# 26_LMS3_RX2_BB_ADC.net
KiCad netlist of a schematic drawn in Altium Designer
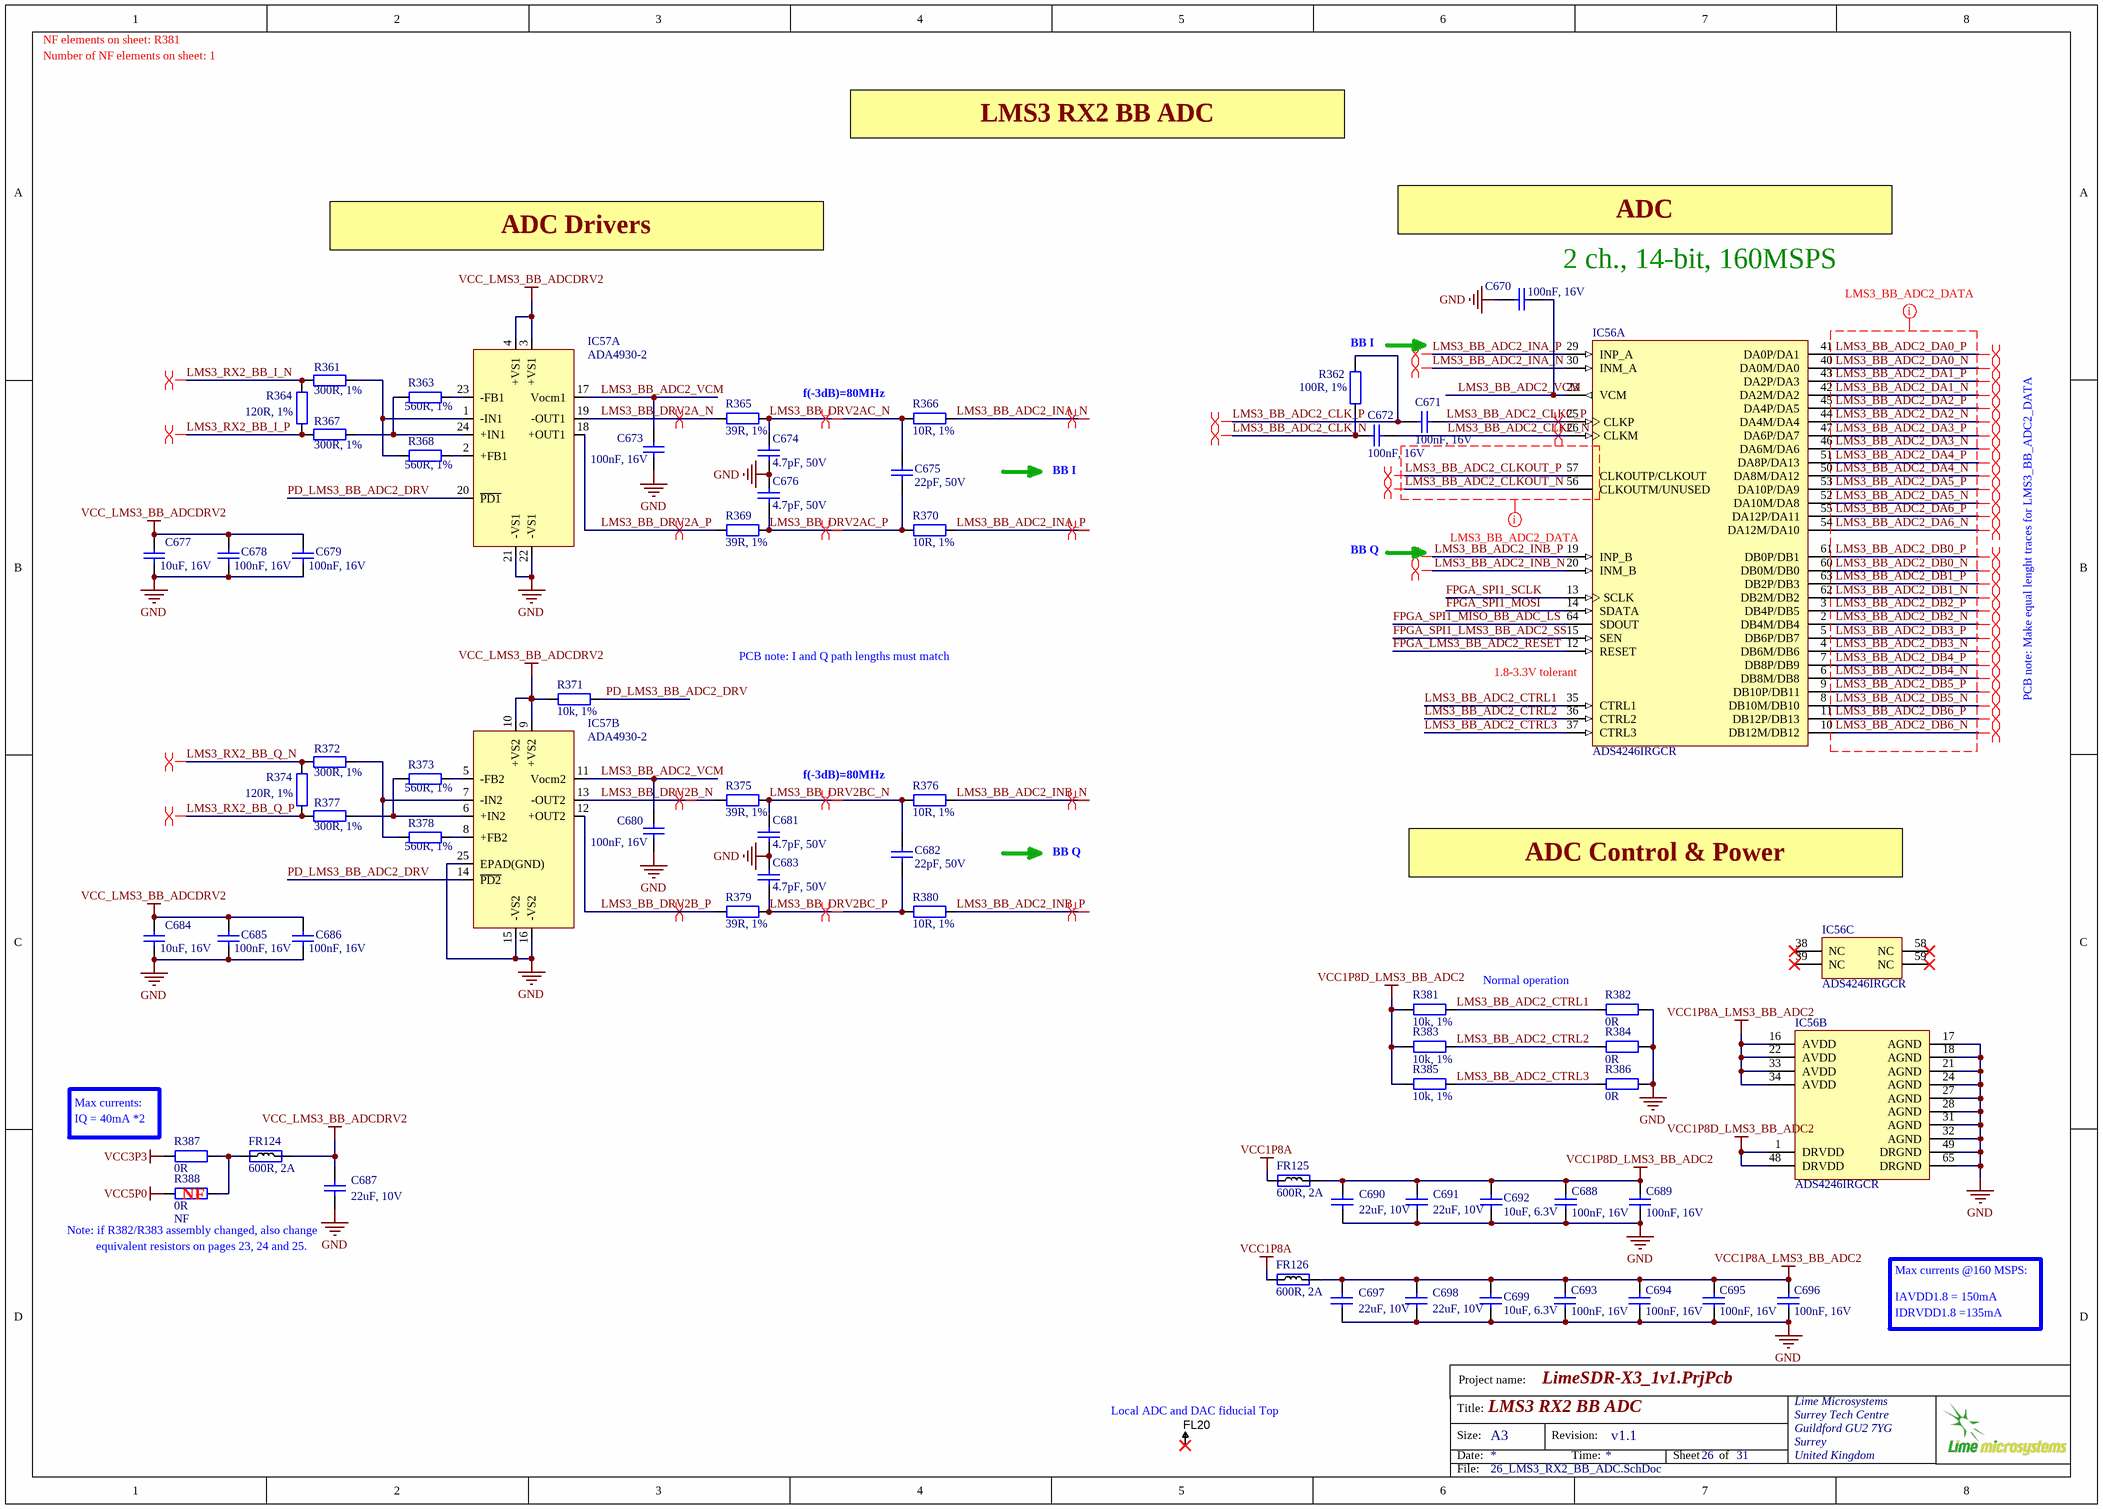
[diagram p0: 26_LMS3_RX2_BB_ADC.SchDoc]

(export (version "E")
  (design (tool "Eeschema 10.0.6"))
  (components
    (comp (ref "C670")
      (value "100nF, 16V")
      (footprint "CAP0402")
      (fields (field (name "TOLERANCE") "10 %") (field (name "MANUFACTURER") "Murata Electronics"))
      (libsource (lib "") (part "Cap_0603_1"))
    )
    (comp (ref "C671")
      (value "100nF, 16V")
      (footprint "CAP0402")
      (fields (field (name "TOLERANCE") "10 %") (field (name "MANUFACTURER") "Murata Electronics"))
      (libsource (lib "") (part "Cap_0603_1"))
    )
    (comp (ref "C672")
      (value "100nF, 16V")
      (footprint "CAP0402")
      (fields (field (name "TOLERANCE") "10 %") (field (name "MANUFACTURER") "Murata Electronics"))
      (libsource (lib "") (part "Cap_0603_4"))
    )
    (comp (ref "C673")
      (value "100nF, 16V")
      (footprint "CAP0402")
      (fields (field (name "TOLERANCE") "10 %") (field (name "MANUFACTURER") "Murata Electronics"))
      (libsource (lib "") (part "Cap_0603_4"))
    )
    (comp (ref "C674")
      (value "4.7pF, 50V")
      (footprint "CAP0402")
      (fields (field (name "MANUFACTURER") "MURATA"))
      (libsource (lib "LimeMicroAltiumLib_schLib") (part "Cap_0402"))
    )
    (comp (ref "C675")
      (value "22pF, 50V")
      (footprint "CAP0402")
      (fields (field (name "TOLERANCE") "±5%") (field (name "MANUFACTURER") "Yageo"))
      (libsource (lib "") (part "Cap_0402_1"))
    )
    (comp (ref "C676")
      (value "4.7pF, 50V")
      (footprint "CAP0402")
      (fields (field (name "MANUFACTURER") "MURATA"))
      (libsource (lib "LimeMicroAltiumLib_schLib") (part "Cap_0402"))
    )
    (comp (ref "C677")
      (value "10uF, 16V")
      (footprint "CAP0603")
      (fields (field (name "MANUFACTURER") "Yageo") (field (name "TOLERANCE") "±20%"))
      (libsource (lib "LimeMicroAltiumLib_schLib") (part "Cap_0603"))
    )
    (comp (ref "C678")
      (value "100nF, 16V")
      (footprint "CAP0402")
      (fields (field (name "TOLERANCE") "10 %") (field (name "MANUFACTURER") "Murata Electronics"))
      (libsource (lib "") (part "Cap_0603_4"))
    )
    (comp (ref "C679")
      (value "100nF, 16V")
      (footprint "CAP0402")
      (fields (field (name "TOLERANCE") "10 %") (field (name "MANUFACTURER") "Murata Electronics"))
      (libsource (lib "") (part "Cap_0603_4"))
    )
    (comp (ref "C680")
      (value "100nF, 16V")
      (footprint "CAP0402")
      (fields (field (name "TOLERANCE") "10 %") (field (name "MANUFACTURER") "Murata Electronics"))
      (libsource (lib "") (part "Cap_0603_7"))
    )
    (comp (ref "C681")
      (value "4.7pF, 50V")
      (footprint "CAP0402")
      (fields (field (name "MANUFACTURER") "MURATA"))
      (libsource (lib "LimeMicroAltiumLib_schLib") (part "Cap_0402"))
    )
    (comp (ref "C682")
      (value "22pF, 50V")
      (footprint "CAP0402")
      (fields (field (name "TOLERANCE") "±5%") (field (name "MANUFACTURER") "Yageo"))
      (libsource (lib "") (part "Cap_0402_1"))
    )
    (comp (ref "C683")
      (value "4.7pF, 50V")
      (footprint "CAP0402")
      (fields (field (name "MANUFACTURER") "MURATA"))
      (libsource (lib "LimeMicroAltiumLib_schLib") (part "Cap_0402"))
    )
    (comp (ref "C684")
      (value "10uF, 16V")
      (footprint "CAP0603")
      (fields (field (name "MANUFACTURER") "Yageo") (field (name "TOLERANCE") "±20%"))
      (libsource (lib "LimeMicroAltiumLib_schLib") (part "Cap_0603"))
    )
    (comp (ref "C685")
      (value "100nF, 16V")
      (footprint "CAP0402")
      (fields (field (name "TOLERANCE") "10 %") (field (name "MANUFACTURER") "Murata Electronics"))
      (libsource (lib "") (part "Cap_0603_4"))
    )
    (comp (ref "C686")
      (value "100nF, 16V")
      (footprint "CAP0402")
      (fields (field (name "TOLERANCE") "10 %") (field (name "MANUFACTURER") "Murata Electronics"))
      (libsource (lib "") (part "Cap_0603_4"))
    )
    (comp (ref "C687")
      (value "22uF, 10V")
      (footprint "CAP0603")
      (fields (field (name "TOLERANCE") "20 %") (field (name "MANUFACTURER") "TDK Corporation"))
      (libsource (lib "") (part "Cap_0603_5"))
    )
    (comp (ref "C688")
      (value "100nF, 16V")
      (footprint "CAP0402")
      (fields (field (name "TOLERANCE") "10 %") (field (name "MANUFACTURER") "Murata Electronics"))
      (libsource (lib "LimeFPGAboard_schLib") (part "Cap_0603"))
    )
    (comp (ref "C689")
      (value "100nF, 16V")
      (footprint "CAP0402")
      (fields (field (name "TOLERANCE") "10 %") (field (name "MANUFACTURER") "Murata Electronics"))
      (libsource (lib "LimeFPGAboard_schLib") (part "Cap_0603"))
    )
    (comp (ref "C690")
      (value "22uF, 10V")
      (footprint "CAP0603")
      (fields (field (name "TOLERANCE") "20 %") (field (name "MANUFACTURER") "TDK Corporation"))
      (libsource (lib "LimeFPGAboard_schLib") (part "Cap_0603"))
    )
    (comp (ref "C691")
      (value "22uF, 10V")
      (footprint "CAP0603")
      (fields (field (name "TOLERANCE") "20 %") (field (name "MANUFACTURER") "TDK Corporation"))
      (libsource (lib "LimeFPGAboard_schLib") (part "Cap_0603"))
    )
    (comp (ref "C692")
      (value "10uF, 6.3V")
      (footprint "CAP0603")
      (fields (field (name "TOLERANCE") "±20%") (field (name "MANUFACTURER") "Yageo"))
      (libsource (lib "") (part "Cap_0603_2"))
    )
    (comp (ref "C693")
      (value "100nF, 16V")
      (footprint "CAP0402")
      (fields (field (name "TOLERANCE") "10 %") (field (name "MANUFACTURER") "Murata Electronics"))
      (libsource (lib "") (part "Cap_0603_3"))
    )
    (comp (ref "C694")
      (value "100nF, 16V")
      (footprint "CAP0402")
      (fields (field (name "TOLERANCE") "10 %") (field (name "MANUFACTURER") "Murata Electronics"))
      (libsource (lib "") (part "Cap_0603_3"))
    )
    (comp (ref "C695")
      (value "100nF, 16V")
      (footprint "CAP0402")
      (fields (field (name "TOLERANCE") "10 %") (field (name "MANUFACTURER") "Murata Electronics"))
      (libsource (lib "") (part "Cap_0603_3"))
    )
    (comp (ref "C696")
      (value "100nF, 16V")
      (footprint "CAP0402")
      (fields (field (name "TOLERANCE") "10 %") (field (name "MANUFACTURER") "Murata Electronics"))
      (libsource (lib "") (part "Cap_0603_3"))
    )
    (comp (ref "C697")
      (value "22uF, 10V")
      (footprint "CAP0603")
      (fields (field (name "TOLERANCE") "20 %") (field (name "MANUFACTURER") "TDK Corporation"))
      (libsource (lib "") (part "Cap_0603_3"))
    )
    (comp (ref "C698")
      (value "22uF, 10V")
      (footprint "CAP0603")
      (fields (field (name "TOLERANCE") "20 %") (field (name "MANUFACTURER") "TDK Corporation"))
      (libsource (lib "") (part "Cap_0603_3"))
    )
    (comp (ref "C699")
      (value "10uF, 6.3V")
      (footprint "CAP0603")
      (fields (field (name "TOLERANCE") "±20%") (field (name "MANUFACTURER") "Yageo"))
      (libsource (lib "") (part "Cap_0603_6"))
    )
    (comp (ref "FL20")
      (value "Fiducial")
      (footprint "Fiducial_local")
      (libsource (lib "LimeMicroAltiumLib_schLib") (part "Fiducial"))
    )
    (comp (ref "FR124")
      (value "600R, 2A")
      (footprint "RES0805")
      (fields (field (name "MANUFACTURER") "TDK Corporation"))
      (libsource (lib "LimeMicroAltiumLib_schLib") (part "Ferrite"))
    )
    (comp (ref "FR125")
      (value "600R, 2A")
      (footprint "RES0805")
      (fields (field (name "MANUFACTURER") "TDK Corporation"))
      (libsource (lib "LimeFPGAboard_schLib") (part "Ferrite"))
    )
    (comp (ref "FR126")
      (value "600R, 2A")
      (footprint "RES0805")
      (fields (field (name "MANUFACTURER") "TDK Corporation"))
      (libsource (lib "LimeFPGAboard_schLib") (part "Ferrite"))
    )
    (comp (ref "IC56")
      (value "ADS4246IRGCR")
      (footprint "TI-RGC64-7400X7400TP_V")
      (description "14-Bit 160 MSPS Dual Low Power ADC, -40 to 85 degC, 64-pin QFN (RGC64), Green (RoHS & no Sb/Br)")
      (fields (field (name "MANUFACTURER") "Texas Instruments"))
      (libsource (lib "LimeMicroAltiumLib_schLib") (part "ADS4246IRGCR"))
    )
    (comp (ref "IC57")
      (value "ADA4930-2")
      (footprint "ADA4930-2_LFCSP-24")
      (fields (field (name "MANUFACTURER") "Analog Devices Inc."))
      (libsource (lib "LimeMicroAltiumLib_schLib") (part "ADA4930-2"))
    )
    (comp (ref "R361")
      (value "300R, 1%")
      (footprint "RES0402")
      (fields (field (name "TOLERANCE") "±1%") (field (name "MANUFACTURER") "Vishay Dale"))
      (libsource (lib "LimeFPGAboard_schLib") (part "Res_0402"))
    )
    (comp (ref "R362")
      (value "100R, 1%")
      (footprint "RES0402")
      (fields (field (name "TOLERANCE") "±1%") (field (name "MANUFACTURER") "Stackpole Electronics Inc."))
      (libsource (lib "LimeFPGAboard_schLib") (part "Res_0402"))
    )
    (comp (ref "R363")
      (value "560R, 1%")
      (footprint "RES0402")
      (fields (field (name "TOLERANCE") "±1%") (field (name "MANUFACTURER") "Vishay Dale"))
      (libsource (lib "LimeFPGAboard_schLib") (part "Res_0402"))
    )
    (comp (ref "R364")
      (value "120R, 1%")
      (footprint "RES0402")
      (fields (field (name "MANUFACTURER") "Yageo") (field (name "TOLERANCE") "1%"))
      (libsource (lib "") (part "Res_0402_1"))
    )
    (comp (ref "R365")
      (value "39R, 1%")
      (footprint "RES0402")
      (fields (field (name "MANUFACTURER") "Yageo") (field (name "TOLERANCE") "1%"))
      (libsource (lib "LimeMicroAltiumLib_schLib") (part "Res_0402"))
    )
    (comp (ref "R366")
      (value "10R, 1%")
      (footprint "RES0402")
      (fields (field (name "TOLERANCE") "1%"))
      (libsource (lib "LimeMicroAltiumLib_schLib") (part "Res_0402"))
    )
    (comp (ref "R367")
      (value "300R, 1%")
      (footprint "RES0402")
      (fields (field (name "TOLERANCE") "±1%") (field (name "MANUFACTURER") "Vishay Dale"))
      (libsource (lib "LimeFPGAboard_schLib") (part "Res_0402"))
    )
    (comp (ref "R368")
      (value "560R, 1%")
      (footprint "RES0402")
      (fields (field (name "TOLERANCE") "±1%") (field (name "MANUFACTURER") "Vishay Dale"))
      (libsource (lib "LimeFPGAboard_schLib") (part "Res_0402"))
    )
    (comp (ref "R369")
      (value "39R, 1%")
      (footprint "RES0402")
      (fields (field (name "MANUFACTURER") "Yageo") (field (name "TOLERANCE") "1%"))
      (libsource (lib "LimeMicroAltiumLib_schLib") (part "Res_0402"))
    )
    (comp (ref "R370")
      (value "10R, 1%")
      (footprint "RES0402")
      (fields (field (name "TOLERANCE") "1%"))
      (libsource (lib "LimeMicroAltiumLib_schLib") (part "Res_0402"))
    )
    (comp (ref "R371")
      (value "10k, 1%")
      (footprint "RES0402")
      (fields (field (name "MANUFACTURER") "Yageo") (field (name "TOLERANCE") "±1%"))
      (libsource (lib "LimeMicroAltiumLib_schLib") (part "Res_0402"))
    )
    (comp (ref "R372")
      (value "300R, 1%")
      (footprint "RES0402")
      (fields (field (name "TOLERANCE") "±1%") (field (name "MANUFACTURER") "Vishay Dale"))
      (libsource (lib "LimeFPGAboard_schLib") (part "Res_0402"))
    )
    (comp (ref "R373")
      (value "560R, 1%")
      (footprint "RES0402")
      (fields (field (name "TOLERANCE") "±1%") (field (name "MANUFACTURER") "Vishay Dale"))
      (libsource (lib "LimeFPGAboard_schLib") (part "Res_0402"))
    )
    (comp (ref "R374")
      (value "120R, 1%")
      (footprint "RES0402")
      (fields (field (name "MANUFACTURER") "Yageo") (field (name "TOLERANCE") "1%"))
      (libsource (lib "") (part "Res_0402_1"))
    )
    (comp (ref "R375")
      (value "39R, 1%")
      (footprint "RES0402")
      (fields (field (name "MANUFACTURER") "Yageo") (field (name "TOLERANCE") "1%"))
      (libsource (lib "LimeMicroAltiumLib_schLib") (part "Res_0402"))
    )
    (comp (ref "R376")
      (value "10R, 1%")
      (footprint "RES0402")
      (fields (field (name "TOLERANCE") "1%"))
      (libsource (lib "LimeMicroAltiumLib_schLib") (part "Res_0402"))
    )
    (comp (ref "R377")
      (value "300R, 1%")
      (footprint "RES0402")
      (fields (field (name "TOLERANCE") "±1%") (field (name "MANUFACTURER") "Vishay Dale"))
      (libsource (lib "LimeFPGAboard_schLib") (part "Res_0402"))
    )
    (comp (ref "R378")
      (value "560R, 1%")
      (footprint "RES0402")
      (fields (field (name "TOLERANCE") "±1%") (field (name "MANUFACTURER") "Vishay Dale"))
      (libsource (lib "LimeFPGAboard_schLib") (part "Res_0402"))
    )
    (comp (ref "R379")
      (value "39R, 1%")
      (footprint "RES0402")
      (fields (field (name "MANUFACTURER") "Yageo") (field (name "TOLERANCE") "1%"))
      (libsource (lib "LimeMicroAltiumLib_schLib") (part "Res_0402"))
    )
    (comp (ref "R380")
      (value "10R, 1%")
      (footprint "RES0402")
      (fields (field (name "TOLERANCE") "1%"))
      (libsource (lib "LimeMicroAltiumLib_schLib") (part "Res_0402"))
    )
    (comp (ref "R381")
      (value "10k, 1%")
      (footprint "RES0402")
      (fields (field (name "MANUFACTURER") "Yageo") (field (name "TOLERANCE") "±1%"))
      (libsource (lib "LimeMicroAltiumLib_schLib") (part "Res_0402"))
    )
    (comp (ref "R382")
      (value "0R")
      (footprint "RES0402")
      (fields (field (name "MANUFACTURER") "Yageo"))
      (libsource (lib "LimeFPGAboard_schLib") (part "Res_0402"))
    )
    (comp (ref "R383")
      (value "10k, 1%")
      (footprint "RES0402")
      (fields (field (name "MANUFACTURER") "Yageo") (field (name "TOLERANCE") "±1%"))
      (libsource (lib "LimeMicroAltiumLib_schLib") (part "Res_0402"))
    )
    (comp (ref "R384")
      (value "0R")
      (footprint "RES0402")
      (fields (field (name "MANUFACTURER") "Yageo"))
      (libsource (lib "LimeFPGAboard_schLib") (part "Res_0402"))
    )
    (comp (ref "R385")
      (value "10k, 1%")
      (footprint "RES0402")
      (fields (field (name "MANUFACTURER") "Yageo") (field (name "TOLERANCE") "±1%"))
      (libsource (lib "LimeMicroAltiumLib_schLib") (part "Res_0402"))
    )
    (comp (ref "R386")
      (value "0R")
      (footprint "RES0402")
      (fields (field (name "MANUFACTURER") "Yageo"))
      (libsource (lib "LimeFPGAboard_schLib") (part "Res_0402"))
    )
    (comp (ref "R387")
      (value "0R")
      (footprint "RES0402")
      (fields (field (name "MANUFACTURER") "Yageo") (field (name "TOLERANCE") "Jumper"))
      (libsource (lib "LimeMicroAltiumLib_schLib") (part "Res_0402"))
    )
    (comp (ref "R388")
      (value "0R")
      (footprint "RES0402")
      (fields
        (field (name "ASSEMBLY INFO") "NF")
        (field (name "MANUFACTURER") "Yageo")
        (field (name "TOLERANCE") "Jumper")
      )
      (libsource (lib "LimeMicroAltiumLib_schLib") (part "Res_0402"))
    )
  )
  (nets
    (net (code "1") (name "/FPGA_LMS3_BB_ADC2_RESET") (class "Default")
      (node (ref "IC56") (pin "12") (pinfunction "RESET_12") (pintype "input"))
    )
    (net (code "2") (name "/FPGA_SPI1_LMS3_BB_ADC2_SS") (class "Default")
      (node (ref "IC56") (pin "15") (pinfunction "SEN_15") (pintype "input"))
    )
    (net (code "3") (name "/FPGA_SPI1_MISO_BB_ADC_LS") (class "Default")
      (node (ref "IC56") (pin "64") (pinfunction "SDOUT_64") (pintype "tri_state"))
    )
    (net (code "4") (name "/FPGA_SPI1_MOSI") (class "Default")
      (node (ref "IC56") (pin "14") (pinfunction "SDATA_14") (pintype "input"))
    )
    (net (code "5") (name "/FPGA_SPI1_SCLK") (class "Default")
      (node (ref "IC56") (pin "13") (pinfunction "SCLK_13") (pintype "input"))
    )
    (net (code "6") (name "/LMS3_BB_ADC2_CLKC_N") (class "Default")
      (node (ref "C672") (pin "1") (pinfunction "1_1") (pintype "passive"))
      (node (ref "IC56") (pin "26") (pinfunction "CLKM_26") (pintype "input"))
    )
    (net (code "7") (name "/LMS3_BB_ADC2_CLKC_P") (class "Default")
      (node (ref "C671") (pin "1") (pinfunction "1_1") (pintype "passive"))
      (node (ref "IC56") (pin "25") (pinfunction "CLKP_25") (pintype "input"))
    )
    (net (code "8") (name "/LMS3_BB_ADC2_CLKOUT_N") (class "Default")
      (node (ref "IC56") (pin "56") (pinfunction "CLKOUTM/UNUSED_56") (pintype "tri_state"))
    )
    (net (code "9") (name "/LMS3_BB_ADC2_CLKOUT_P") (class "Default")
      (node (ref "IC56") (pin "57") (pinfunction "CLKOUTP/CLKOUT_57") (pintype "tri_state"))
    )
    (net (code "10") (name "/LMS3_BB_ADC2_CLK_N") (class "Default")
      (node (ref "C672") (pin "2") (pinfunction "2_2") (pintype "passive"))
      (node (ref "R362") (pin "1") (pinfunction "1_1") (pintype "passive"))
    )
    (net (code "11") (name "/LMS3_BB_ADC2_CLK_P") (class "Default")
      (node (ref "C671") (pin "2") (pinfunction "2_2") (pintype "passive"))
      (node (ref "R362") (pin "2") (pinfunction "2_2") (pintype "passive"))
    )
    (net (code "12") (name "/LMS3_BB_ADC2_CTRL1") (class "Default")
      (node (ref "IC56") (pin "35") (pinfunction "CTRL1_35") (pintype "input"))
      (node (ref "R381") (pin "1") (pinfunction "1_1") (pintype "passive"))
      (node (ref "R382") (pin "2") (pinfunction "2_2") (pintype "passive"))
    )
    (net (code "13") (name "/LMS3_BB_ADC2_CTRL2") (class "Default")
      (node (ref "IC56") (pin "36") (pinfunction "CTRL2_36") (pintype "input"))
      (node (ref "R383") (pin "1") (pinfunction "1_1") (pintype "passive"))
      (node (ref "R384") (pin "2") (pinfunction "2_2") (pintype "passive"))
    )
    (net (code "14") (name "/LMS3_BB_ADC2_CTRL3") (class "Default")
      (node (ref "IC56") (pin "37") (pinfunction "CTRL3_37") (pintype "input"))
      (node (ref "R385") (pin "1") (pinfunction "1_1") (pintype "passive"))
      (node (ref "R386") (pin "2") (pinfunction "2_2") (pintype "passive"))
    )
    (net (code "15") (name "/LMS3_BB_ADC2_DA0_N") (class "Default")
      (node (ref "IC56") (pin "40") (pinfunction "DA0M/DA0_40") (pintype "tri_state"))
    )
    (net (code "16") (name "/LMS3_BB_ADC2_DA0_P") (class "Default")
      (node (ref "IC56") (pin "41") (pinfunction "DA0P/DA1_41") (pintype "tri_state"))
    )
    (net (code "17") (name "/LMS3_BB_ADC2_DA1_N") (class "Default")
      (node (ref "IC56") (pin "42") (pinfunction "DA2M/DA2_42") (pintype "tri_state"))
    )
    (net (code "18") (name "/LMS3_BB_ADC2_DA1_P") (class "Default")
      (node (ref "IC56") (pin "43") (pinfunction "DA2P/DA3_43") (pintype "tri_state"))
    )
    (net (code "19") (name "/LMS3_BB_ADC2_DA2_N") (class "Default")
      (node (ref "IC56") (pin "44") (pinfunction "DA4M/DA4_44") (pintype "tri_state"))
    )
    (net (code "20") (name "/LMS3_BB_ADC2_DA2_P") (class "Default")
      (node (ref "IC56") (pin "45") (pinfunction "DA4P/DA5_45") (pintype "tri_state"))
    )
    (net (code "21") (name "/LMS3_BB_ADC2_DA3_N") (class "Default")
      (node (ref "IC56") (pin "46") (pinfunction "DA6M/DA6_46") (pintype "tri_state"))
    )
    (net (code "22") (name "/LMS3_BB_ADC2_DA3_P") (class "Default")
      (node (ref "IC56") (pin "47") (pinfunction "DA6P/DA7_47") (pintype "tri_state"))
    )
    (net (code "23") (name "/LMS3_BB_ADC2_DA4_N") (class "Default")
      (node (ref "IC56") (pin "50") (pinfunction "DA8M/DA12_50") (pintype "tri_state"))
    )
    (net (code "24") (name "/LMS3_BB_ADC2_DA4_P") (class "Default")
      (node (ref "IC56") (pin "51") (pinfunction "DA8P/DA13_51") (pintype "tri_state"))
    )
    (net (code "25") (name "/LMS3_BB_ADC2_DA5_N") (class "Default")
      (node (ref "IC56") (pin "52") (pinfunction "DA10M/DA8_52") (pintype "tri_state"))
    )
    (net (code "26") (name "/LMS3_BB_ADC2_DA5_P") (class "Default")
      (node (ref "IC56") (pin "53") (pinfunction "DA10P/DA9_53") (pintype "tri_state"))
    )
    (net (code "27") (name "/LMS3_BB_ADC2_DA6_N") (class "Default")
      (node (ref "IC56") (pin "54") (pinfunction "DA12M/DA10_54") (pintype "tri_state"))
    )
    (net (code "28") (name "/LMS3_BB_ADC2_DA6_P") (class "Default")
      (node (ref "IC56") (pin "55") (pinfunction "DA12P/DA11_55") (pintype "tri_state"))
    )
    (net (code "29") (name "/LMS3_BB_ADC2_DB0_N") (class "Default")
      (node (ref "IC56") (pin "60") (pinfunction "DB0M/DB0_60") (pintype "tri_state"))
    )
    (net (code "30") (name "/LMS3_BB_ADC2_DB0_P") (class "Default")
      (node (ref "IC56") (pin "61") (pinfunction "DB0P/DB1_61") (pintype "tri_state"))
    )
    (net (code "31") (name "/LMS3_BB_ADC2_DB1_N") (class "Default")
      (node (ref "IC56") (pin "62") (pinfunction "DB2M/DB2_62") (pintype "tri_state"))
    )
    (net (code "32") (name "/LMS3_BB_ADC2_DB1_P") (class "Default")
      (node (ref "IC56") (pin "63") (pinfunction "DB2P/DB3_63") (pintype "tri_state"))
    )
    (net (code "33") (name "/LMS3_BB_ADC2_DB2_N") (class "Default")
      (node (ref "IC56") (pin "2") (pinfunction "DB4M/DB4_2") (pintype "tri_state"))
    )
    (net (code "34") (name "/LMS3_BB_ADC2_DB2_P") (class "Default")
      (node (ref "IC56") (pin "3") (pinfunction "DB4P/DB5_3") (pintype "tri_state"))
    )
    (net (code "35") (name "/LMS3_BB_ADC2_DB3_N") (class "Default")
      (node (ref "IC56") (pin "4") (pinfunction "DB6M/DB6_4") (pintype "tri_state"))
    )
    (net (code "36") (name "/LMS3_BB_ADC2_DB3_P") (class "Default")
      (node (ref "IC56") (pin "5") (pinfunction "DB6P/DB7_5") (pintype "tri_state"))
    )
    (net (code "37") (name "/LMS3_BB_ADC2_DB4_N") (class "Default")
      (node (ref "IC56") (pin "6") (pinfunction "DB8M/DB8_6") (pintype "tri_state"))
    )
    (net (code "38") (name "/LMS3_BB_ADC2_DB4_P") (class "Default")
      (node (ref "IC56") (pin "7") (pinfunction "DB8P/DB9_7") (pintype "tri_state"))
    )
    (net (code "39") (name "/LMS3_BB_ADC2_DB5_N") (class "Default")
      (node (ref "IC56") (pin "8") (pinfunction "DB10M/DB10_8") (pintype "tri_state"))
    )
    (net (code "40") (name "/LMS3_BB_ADC2_DB5_P") (class "Default")
      (node (ref "IC56") (pin "9") (pinfunction "DB10P/DB11_9") (pintype "tri_state"))
    )
    (net (code "41") (name "/LMS3_BB_ADC2_DB6_N") (class "Default")
      (node (ref "IC56") (pin "10") (pinfunction "DB12M/DB12_10") (pintype "tri_state"))
    )
    (net (code "42") (name "/LMS3_BB_ADC2_DB6_P") (class "Default")
      (node (ref "IC56") (pin "11") (pinfunction "DB12P/DB13_11") (pintype "tri_state"))
    )
    (net (code "43") (name "/LMS3_BB_ADC2_INA_N") (class "Default")
      (node (ref "IC56") (pin "30") (pinfunction "INM_A_30") (pintype "input"))
      (node (ref "R366") (pin "1") (pinfunction "1_1") (pintype "passive"))
    )
    (net (code "44") (name "/LMS3_BB_ADC2_INA_P") (class "Default")
      (node (ref "IC56") (pin "29") (pinfunction "INP_A_29") (pintype "input"))
      (node (ref "R370") (pin "1") (pinfunction "1_1") (pintype "passive"))
    )
    (net (code "45") (name "/LMS3_BB_ADC2_INB_N") (class "Default")
      (node (ref "IC56") (pin "20") (pinfunction "INM_B_20") (pintype "input"))
      (node (ref "R376") (pin "1") (pinfunction "1_1") (pintype "passive"))
    )
    (net (code "46") (name "/LMS3_BB_ADC2_INB_P") (class "Default")
      (node (ref "IC56") (pin "19") (pinfunction "INP_B_19") (pintype "input"))
      (node (ref "R380") (pin "1") (pinfunction "1_1") (pintype "passive"))
    )
    (net (code "47") (name "/LMS3_BB_ADC2_VCM") (class "Default")
      (node (ref "C670") (pin "2") (pinfunction "2_2") (pintype "passive"))
      (node (ref "C673") (pin "1") (pinfunction "1_1") (pintype "passive"))
      (node (ref "C680") (pin "1") (pinfunction "1_1") (pintype "passive"))
      (node (ref "IC56") (pin "23") (pinfunction "VCM_23") (pintype "output"))
      (node (ref "IC57") (pin "11") (pinfunction "Vocm2_11") (pintype "input"))
      (node (ref "IC57") (pin "17") (pinfunction "Vocm1_17") (pintype "input"))
    )
    (net (code "48") (name "/LMS3_BB_DRV2AC_N") (class "Default")
      (node (ref "C674") (pin "1") (pinfunction "1_1") (pintype "passive"))
      (node (ref "C675") (pin "1") (pinfunction "1_1") (pintype "passive"))
      (node (ref "R365") (pin "1") (pinfunction "1_1") (pintype "passive"))
      (node (ref "R366") (pin "2") (pinfunction "2_2") (pintype "passive"))
    )
    (net (code "49") (name "/LMS3_BB_DRV2AC_P") (class "Default")
      (node (ref "C675") (pin "2") (pinfunction "2_2") (pintype "passive"))
      (node (ref "C676") (pin "2") (pinfunction "2_2") (pintype "passive"))
      (node (ref "R369") (pin "1") (pinfunction "1_1") (pintype "passive"))
      (node (ref "R370") (pin "2") (pinfunction "2_2") (pintype "passive"))
    )
    (net (code "50") (name "/LMS3_BB_DRV2A_N") (class "Default")
      (node (ref "IC57") (pin "19") (pinfunction "-OUT1_19") (pintype "output"))
      (node (ref "R365") (pin "2") (pinfunction "2_2") (pintype "passive"))
    )
    (net (code "51") (name "/LMS3_BB_DRV2A_P") (class "Default")
      (node (ref "IC57") (pin "18") (pinfunction "+OUT1_18") (pintype "output"))
      (node (ref "R369") (pin "2") (pinfunction "2_2") (pintype "passive"))
    )
    (net (code "52") (name "/LMS3_BB_DRV2BC_N") (class "Default")
      (node (ref "C681") (pin "1") (pinfunction "1_1") (pintype "passive"))
      (node (ref "C682") (pin "1") (pinfunction "1_1") (pintype "passive"))
      (node (ref "R375") (pin "1") (pinfunction "1_1") (pintype "passive"))
      (node (ref "R376") (pin "2") (pinfunction "2_2") (pintype "passive"))
    )
    (net (code "53") (name "/LMS3_BB_DRV2BC_P") (class "Default")
      (node (ref "C682") (pin "2") (pinfunction "2_2") (pintype "passive"))
      (node (ref "C683") (pin "2") (pinfunction "2_2") (pintype "passive"))
      (node (ref "R379") (pin "1") (pinfunction "1_1") (pintype "passive"))
      (node (ref "R380") (pin "2") (pinfunction "2_2") (pintype "passive"))
    )
    (net (code "54") (name "/LMS3_BB_DRV2B_N") (class "Default")
      (node (ref "IC57") (pin "13") (pinfunction "-OUT2_13") (pintype "output"))
      (node (ref "R375") (pin "2") (pinfunction "2_2") (pintype "passive"))
    )
    (net (code "55") (name "/LMS3_BB_DRV2B_P") (class "Default")
      (node (ref "IC57") (pin "12") (pinfunction "+OUT2_12") (pintype "output"))
      (node (ref "R379") (pin "2") (pinfunction "2_2") (pintype "passive"))
    )
    (net (code "56") (name "/LMS3_RX2_BB_I_N") (class "Default")
      (node (ref "R361") (pin "2") (pinfunction "2_2") (pintype "passive"))
      (node (ref "R364") (pin "2") (pinfunction "2_2") (pintype "passive"))
    )
    (net (code "57") (name "/LMS3_RX2_BB_I_P") (class "Default")
      (node (ref "R364") (pin "1") (pinfunction "1_1") (pintype "passive"))
      (node (ref "R367") (pin "2") (pinfunction "2_2") (pintype "passive"))
    )
    (net (code "58") (name "/LMS3_RX2_BB_Q_N") (class "Default")
      (node (ref "R372") (pin "2") (pinfunction "2_2") (pintype "passive"))
      (node (ref "R374") (pin "2") (pinfunction "2_2") (pintype "passive"))
    )
    (net (code "59") (name "/LMS3_RX2_BB_Q_P") (class "Default")
      (node (ref "R374") (pin "1") (pinfunction "1_1") (pintype "passive"))
      (node (ref "R377") (pin "2") (pinfunction "2_2") (pintype "passive"))
    )
    (net (code "60") (name "/PD_LMS3_BB_ADC2_DRV") (class "Default")
      (node (ref "IC57") (pin "14") (pinfunction "~{PD2}_14") (pintype "input"))
      (node (ref "IC57") (pin "20") (pinfunction "~{PD1}_20") (pintype "input"))
      (node (ref "R371") (pin "1") (pinfunction "1_1") (pintype "passive"))
    )
    (net (code "61") (name "GND") (class "Default")
      (node (ref "C670") (pin "1") (pinfunction "1_1") (pintype "passive"))
      (node (ref "C673") (pin "2") (pinfunction "2_2") (pintype "passive"))
      (node (ref "C674") (pin "2") (pinfunction "2_2") (pintype "passive"))
      (node (ref "C676") (pin "1") (pinfunction "1_1") (pintype "passive"))
      (node (ref "C677") (pin "1") (pinfunction "1_1") (pintype "passive"))
      (node (ref "C678") (pin "2") (pinfunction "2_2") (pintype "passive"))
      (node (ref "C679") (pin "2") (pinfunction "2_2") (pintype "passive"))
      (node (ref "C680") (pin "2") (pinfunction "2_2") (pintype "passive"))
      (node (ref "C681") (pin "2") (pinfunction "2_2") (pintype "passive"))
      (node (ref "C683") (pin "1") (pinfunction "1_1") (pintype "passive"))
      (node (ref "C684") (pin "1") (pinfunction "1_1") (pintype "passive"))
      (node (ref "C685") (pin "2") (pinfunction "2_2") (pintype "passive"))
      (node (ref "C686") (pin "2") (pinfunction "2_2") (pintype "passive"))
      (node (ref "C687") (pin "1") (pinfunction "1_1") (pintype "passive"))
      (node (ref "C688") (pin "1") (pinfunction "1_1") (pintype "passive"))
      (node (ref "C689") (pin "1") (pinfunction "1_1") (pintype "passive"))
      (node (ref "C690") (pin "1") (pinfunction "1_1") (pintype "passive"))
      (node (ref "C691") (pin "1") (pinfunction "1_1") (pintype "passive"))
      (node (ref "C692") (pin "2") (pinfunction "2_2") (pintype "passive"))
      (node (ref "C693") (pin "1") (pinfunction "1_1") (pintype "passive"))
      (node (ref "C694") (pin "1") (pinfunction "1_1") (pintype "passive"))
      (node (ref "C695") (pin "1") (pinfunction "1_1") (pintype "passive"))
      (node (ref "C696") (pin "1") (pinfunction "1_1") (pintype "passive"))
      (node (ref "C697") (pin "1") (pinfunction "1_1") (pintype "passive"))
      (node (ref "C698") (pin "1") (pinfunction "1_1") (pintype "passive"))
      (node (ref "C699") (pin "2") (pinfunction "2_2") (pintype "passive"))
      (node (ref "IC56") (pin "17") (pinfunction "AGND_17") (pintype "power_in"))
      (node (ref "IC56") (pin "18") (pinfunction "AGND_18") (pintype "power_in"))
      (node (ref "IC56") (pin "21") (pinfunction "AGND_21") (pintype "power_in"))
      (node (ref "IC56") (pin "24") (pinfunction "AGND_24") (pintype "power_in"))
      (node (ref "IC56") (pin "27") (pinfunction "AGND_27") (pintype "power_in"))
      (node (ref "IC56") (pin "28") (pinfunction "AGND_28") (pintype "power_in"))
      (node (ref "IC56") (pin "31") (pinfunction "AGND_31") (pintype "power_in"))
      (node (ref "IC56") (pin "32") (pinfunction "AGND_32") (pintype "power_in"))
      (node (ref "IC56") (pin "49") (pinfunction "DRGND_49") (pintype "power_in"))
      (node (ref "IC56") (pin "65") (pinfunction "DRGND_65") (pintype "power_in"))
      (node (ref "IC57") (pin "15") (pinfunction "-VS2_15") (pintype "power_in"))
      (node (ref "IC57") (pin "16") (pinfunction "-VS2_16") (pintype "power_in"))
      (node (ref "IC57") (pin "21") (pinfunction "-VS1_21") (pintype "power_in"))
      (node (ref "IC57") (pin "22") (pinfunction "-VS1_22") (pintype "power_in"))
      (node (ref "IC57") (pin "25") (pinfunction "EPAD(GND)_25") (pintype "passive"))
      (node (ref "R382") (pin "1") (pinfunction "1_1") (pintype "passive"))
      (node (ref "R384") (pin "1") (pinfunction "1_1") (pintype "passive"))
      (node (ref "R386") (pin "1") (pinfunction "1_1") (pintype "passive"))
    )
    (net (code "62") (name "Net-(FR124-Pad1)") (class "Default")
      (node (ref "FR124") (pin "1") (pinfunction "1_1") (pintype "passive"))
      (node (ref "R387") (pin "1") (pinfunction "1_1") (pintype "passive"))
      (node (ref "R388") (pin "1") (pinfunction "1_1") (pintype "passive"))
    )
    (net (code "63") (name "Net-(IC57A-+FB1)") (class "Default")
      (node (ref "IC57") (pin "2") (pinfunction "+FB1_2") (pintype "output"))
      (node (ref "R368") (pin "1") (pinfunction "1_1") (pintype "passive"))
    )
    (net (code "64") (name "Net-(IC57A-+IN1)") (class "Default")
      (node (ref "IC57") (pin "24") (pinfunction "+IN1_24") (pintype "input"))
      (node (ref "R363") (pin "2") (pinfunction "2_2") (pintype "passive"))
      (node (ref "R367") (pin "1") (pinfunction "1_1") (pintype "passive"))
    )
    (net (code "65") (name "Net-(IC57A--FB1)") (class "Default")
      (node (ref "IC57") (pin "23") (pinfunction "-FB1_23") (pintype "output"))
      (node (ref "R363") (pin "1") (pinfunction "1_1") (pintype "passive"))
    )
    (net (code "66") (name "Net-(IC57A--IN1)") (class "Default")
      (node (ref "IC57") (pin "1") (pinfunction "-IN1_1") (pintype "input"))
      (node (ref "R361") (pin "1") (pinfunction "1_1") (pintype "passive"))
      (node (ref "R368") (pin "2") (pinfunction "2_2") (pintype "passive"))
    )
    (net (code "67") (name "Net-(IC57B-+FB2)") (class "Default")
      (node (ref "IC57") (pin "8") (pinfunction "+FB2_8") (pintype "output"))
      (node (ref "R378") (pin "1") (pinfunction "1_1") (pintype "passive"))
    )
    (net (code "68") (name "Net-(IC57B-+IN2)") (class "Default")
      (node (ref "IC57") (pin "6") (pinfunction "+IN2_6") (pintype "input"))
      (node (ref "R373") (pin "2") (pinfunction "2_2") (pintype "passive"))
      (node (ref "R377") (pin "1") (pinfunction "1_1") (pintype "passive"))
    )
    (net (code "69") (name "Net-(IC57B--FB2)") (class "Default")
      (node (ref "IC57") (pin "5") (pinfunction "-FB2_5") (pintype "output"))
      (node (ref "R373") (pin "1") (pinfunction "1_1") (pintype "passive"))
    )
    (net (code "70") (name "Net-(IC57B--IN2)") (class "Default")
      (node (ref "IC57") (pin "7") (pinfunction "-IN2_7") (pintype "input"))
      (node (ref "R372") (pin "1") (pinfunction "1_1") (pintype "passive"))
      (node (ref "R378") (pin "2") (pinfunction "2_2") (pintype "passive"))
    )
    (net (code "71") (name "VCC1P8A") (class "Default")
      (node (ref "FR125") (pin "1") (pinfunction "1_1") (pintype "passive"))
      (node (ref "FR126") (pin "1") (pinfunction "1_1") (pintype "passive"))
    )
    (net (code "72") (name "VCC1P8A_LMS3_BB_ADC2") (class "Default")
      (node (ref "C693") (pin "2") (pinfunction "2_2") (pintype "passive"))
      (node (ref "C694") (pin "2") (pinfunction "2_2") (pintype "passive"))
      (node (ref "C695") (pin "2") (pinfunction "2_2") (pintype "passive"))
      (node (ref "C696") (pin "2") (pinfunction "2_2") (pintype "passive"))
      (node (ref "C697") (pin "2") (pinfunction "2_2") (pintype "passive"))
      (node (ref "C698") (pin "2") (pinfunction "2_2") (pintype "passive"))
      (node (ref "C699") (pin "1") (pinfunction "1_1") (pintype "passive"))
      (node (ref "FR126") (pin "2") (pinfunction "2_2") (pintype "passive"))
      (node (ref "IC56") (pin "16") (pinfunction "AVDD_16") (pintype "power_in"))
      (node (ref "IC56") (pin "22") (pinfunction "AVDD_22") (pintype "power_in"))
      (node (ref "IC56") (pin "33") (pinfunction "AVDD_33") (pintype "power_in"))
      (node (ref "IC56") (pin "34") (pinfunction "AVDD_34") (pintype "power_in"))
    )
    (net (code "73") (name "VCC1P8D_LMS3_BB_ADC2") (class "Default")
      (node (ref "C688") (pin "2") (pinfunction "2_2") (pintype "passive"))
      (node (ref "C689") (pin "2") (pinfunction "2_2") (pintype "passive"))
      (node (ref "C690") (pin "2") (pinfunction "2_2") (pintype "passive"))
      (node (ref "C691") (pin "2") (pinfunction "2_2") (pintype "passive"))
      (node (ref "C692") (pin "1") (pinfunction "1_1") (pintype "passive"))
      (node (ref "FR125") (pin "2") (pinfunction "2_2") (pintype "passive"))
      (node (ref "IC56") (pin "1") (pinfunction "DRVDD_1") (pintype "power_in"))
      (node (ref "IC56") (pin "48") (pinfunction "DRVDD_48") (pintype "power_in"))
      (node (ref "R381") (pin "2") (pinfunction "2_2") (pintype "passive"))
      (node (ref "R383") (pin "2") (pinfunction "2_2") (pintype "passive"))
      (node (ref "R385") (pin "2") (pinfunction "2_2") (pintype "passive"))
    )
    (net (code "74") (name "VCC3P3") (class "Default")
      (node (ref "R387") (pin "2") (pinfunction "2_2") (pintype "passive"))
    )
    (net (code "75") (name "VCC5P0") (class "Default")
      (node (ref "R388") (pin "2") (pinfunction "2_2") (pintype "passive"))
    )
    (net (code "76") (name "VCC_LMS3_BB_ADCDRV2") (class "Default")
      (node (ref "C677") (pin "2") (pinfunction "2_2") (pintype "passive"))
      (node (ref "C678") (pin "1") (pinfunction "1_1") (pintype "passive"))
      (node (ref "C679") (pin "1") (pinfunction "1_1") (pintype "passive"))
      (node (ref "C684") (pin "2") (pinfunction "2_2") (pintype "passive"))
      (node (ref "C685") (pin "1") (pinfunction "1_1") (pintype "passive"))
      (node (ref "C686") (pin "1") (pinfunction "1_1") (pintype "passive"))
      (node (ref "C687") (pin "2") (pinfunction "2_2") (pintype "passive"))
      (node (ref "FR124") (pin "2") (pinfunction "2_2") (pintype "passive"))
      (node (ref "IC57") (pin "10") (pinfunction "+VS2_10") (pintype "power_in"))
      (node (ref "IC57") (pin "3") (pinfunction "+VS1_3") (pintype "power_in"))
      (node (ref "IC57") (pin "4") (pinfunction "+VS1_4") (pintype "power_in"))
      (node (ref "IC57") (pin "9") (pinfunction "+VS2_9") (pintype "power_in"))
      (node (ref "R371") (pin "2") (pinfunction "2_2") (pintype "passive"))
    )
    (net (code "77") (name "unconnected-(FL20-Pad1)") (class "Default")
      (node (ref "FL20") (pin "1") (pintype "passive+no_connect"))
    )
    (net (code "78") (name "unconnected-(IC56C-NC-Pad38)") (class "Default")
      (node (ref "IC56") (pin "38") (pinfunction "NC_38") (pintype "passive+no_connect"))
    )
    (net (code "79") (name "unconnected-(IC56C-NC-Pad39)") (class "Default")
      (node (ref "IC56") (pin "39") (pinfunction "NC_39") (pintype "passive+no_connect"))
    )
    (net (code "80") (name "unconnected-(IC56C-NC-Pad58)") (class "Default")
      (node (ref "IC56") (pin "58") (pinfunction "NC_58") (pintype "passive+no_connect"))
    )
    (net (code "81") (name "unconnected-(IC56C-NC-Pad59)") (class "Default")
      (node (ref "IC56") (pin "59") (pinfunction "NC_59") (pintype "passive+no_connect"))
    )
  )
)
